# 01_cover_page.net
KiCad netlist of a schematic drawn in Altium Designer
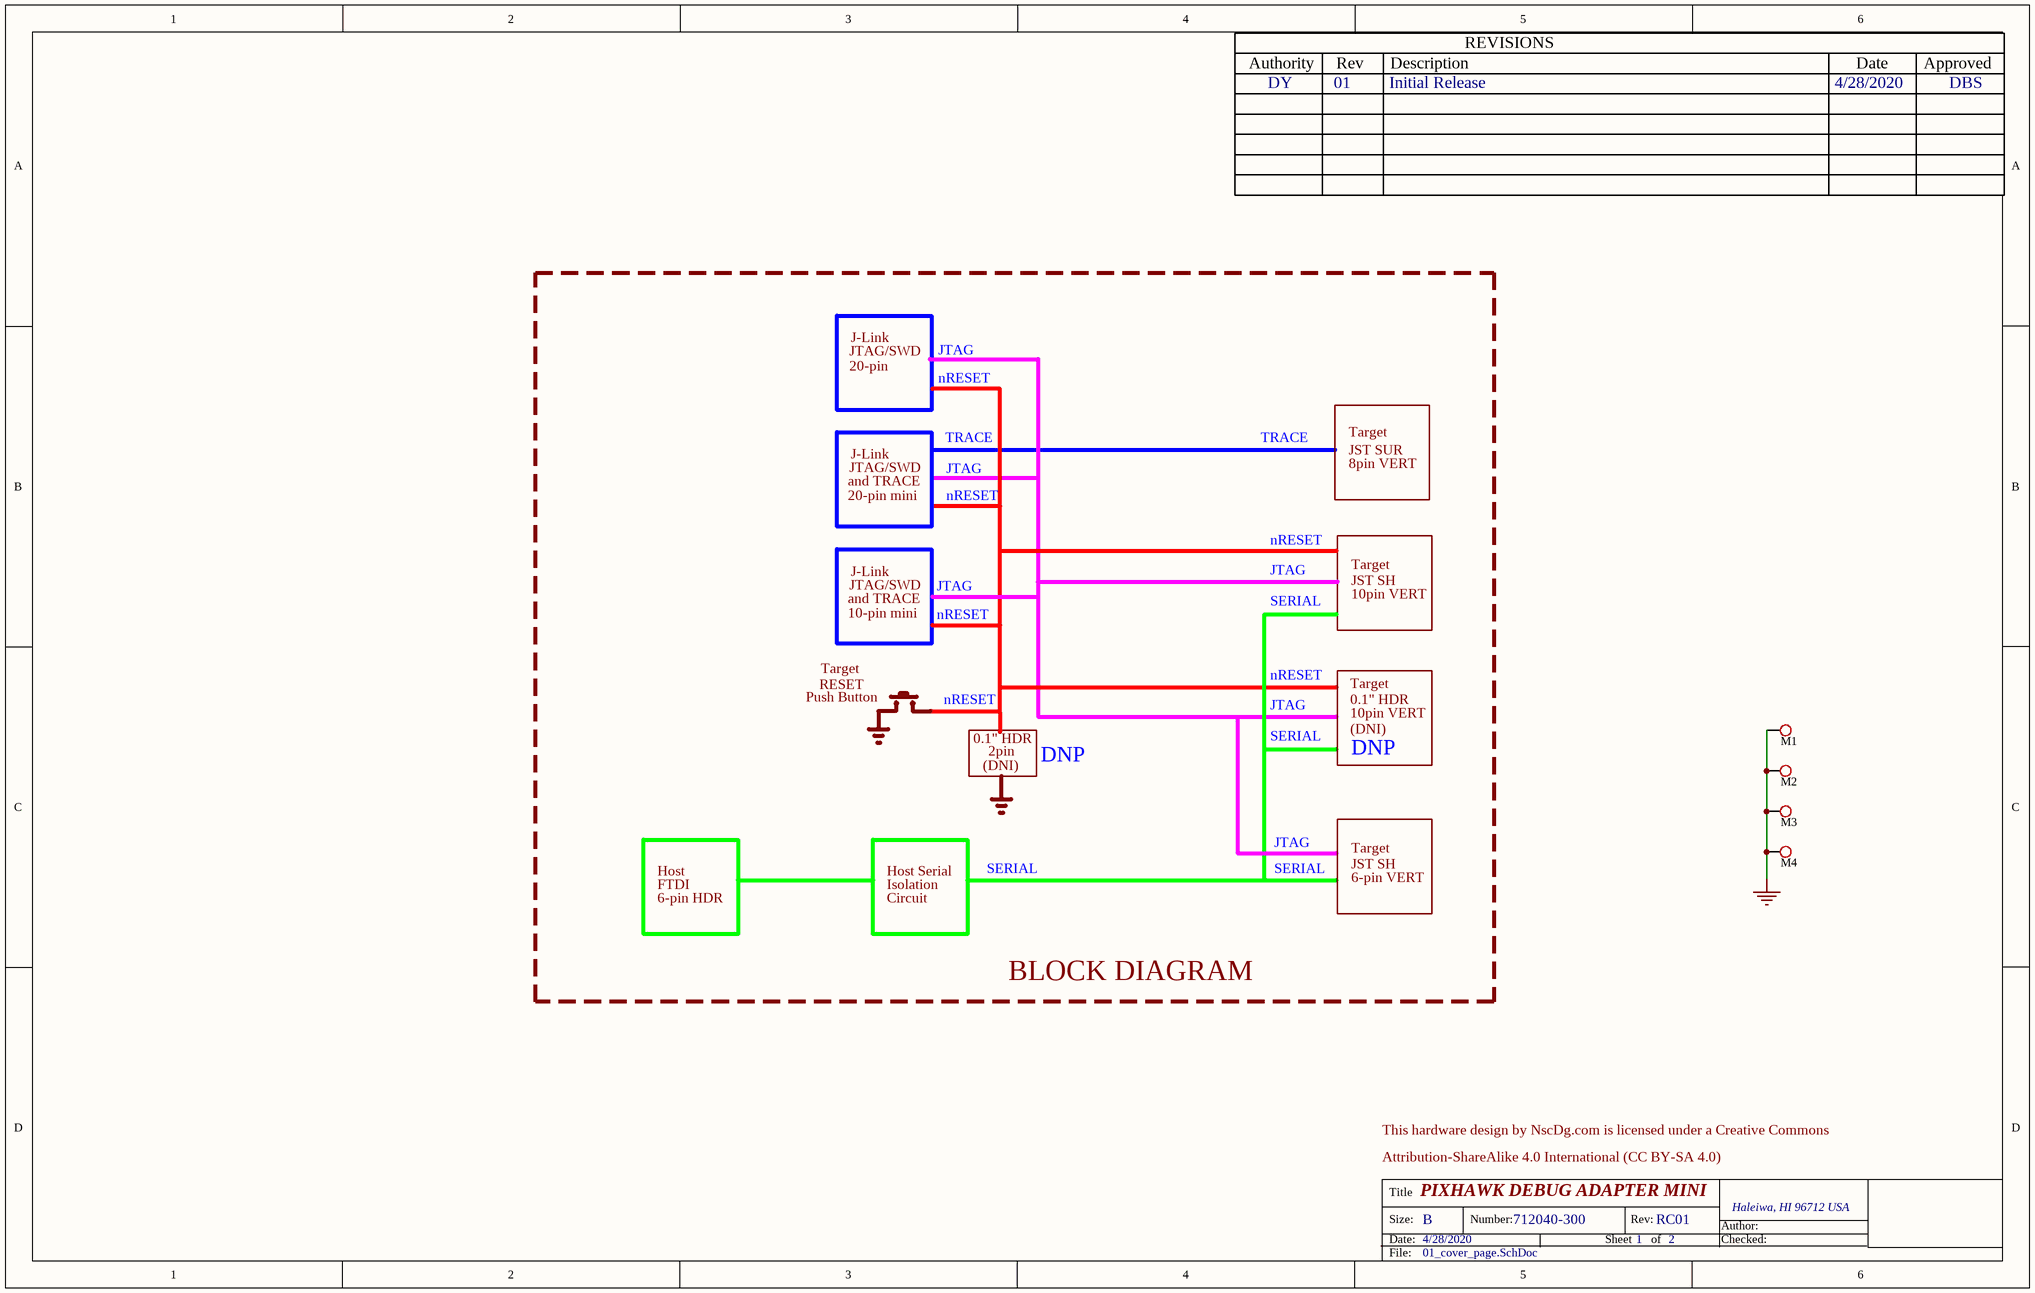
[diagram p0: 01_cover_page.SchDoc]

(export (version "E")
  (design (tool "Eeschema 10.0.6"))
  (components
    (comp (ref "*") (value "REVISION_BLOCK") (libsource (lib "JtagDebug") (part "REVISION_BLOCK")))
    (comp (ref "M1")
      (value "MOUNT HOLE 3MM 8VIAS THMOUNT_HOLE_3MM_TH")
      (footprint "MOUNT_HOLE_3MM_8via_TH")
      (description "MOUNT HOLE 3MM 8VIAS TH")
      (libsource (lib "My_Integrated_Library") (part "MOUNT_HOLE_3MM_8VIAS_TH"))
    )
    (comp (ref "M2")
      (value "MOUNT HOLE 3MM 8VIAS THMOUNT_HOLE_3MM_TH")
      (footprint "MOUNT_HOLE_3MM_8via_TH")
      (description "MOUNT HOLE 3MM 8VIAS TH")
      (libsource (lib "My_Integrated_Library") (part "MOUNT_HOLE_3MM_8VIAS_TH"))
    )
    (comp (ref "M3")
      (value "MOUNT HOLE 3MM 8VIAS THMOUNT_HOLE_3MM_TH")
      (footprint "MOUNT_HOLE_3MM_8via_TH")
      (description "MOUNT HOLE 3MM 8VIAS TH")
      (libsource (lib "My_Integrated_Library") (part "MOUNT_HOLE_3MM_8VIAS_TH"))
    )
    (comp (ref "M4")
      (value "MOUNT HOLE 3MM 8VIAS THMOUNT_HOLE_3MM_TH")
      (footprint "MOUNT_HOLE_3MM_8via_TH")
      (description "MOUNT HOLE 3MM 8VIAS TH")
      (libsource (lib "My_Integrated_Library") (part "MOUNT_HOLE_3MM_8VIAS_TH"))
    )
  )
  (nets
    (net (code "1") (name "GND") (class "Default")
      (node (ref "M1") (pin "1") (pinfunction "1_1") (pintype "passive"))
      (node (ref "M2") (pin "1") (pinfunction "1_1") (pintype "passive"))
      (node (ref "M3") (pin "1") (pinfunction "1_1") (pintype "passive"))
      (node (ref "M4") (pin "1") (pinfunction "1_1") (pintype "passive"))
    )
  )
)
